# SAMV71_Xplained_Ultra_Audio.net
KiCad netlist of a schematic drawn in Altium Designer
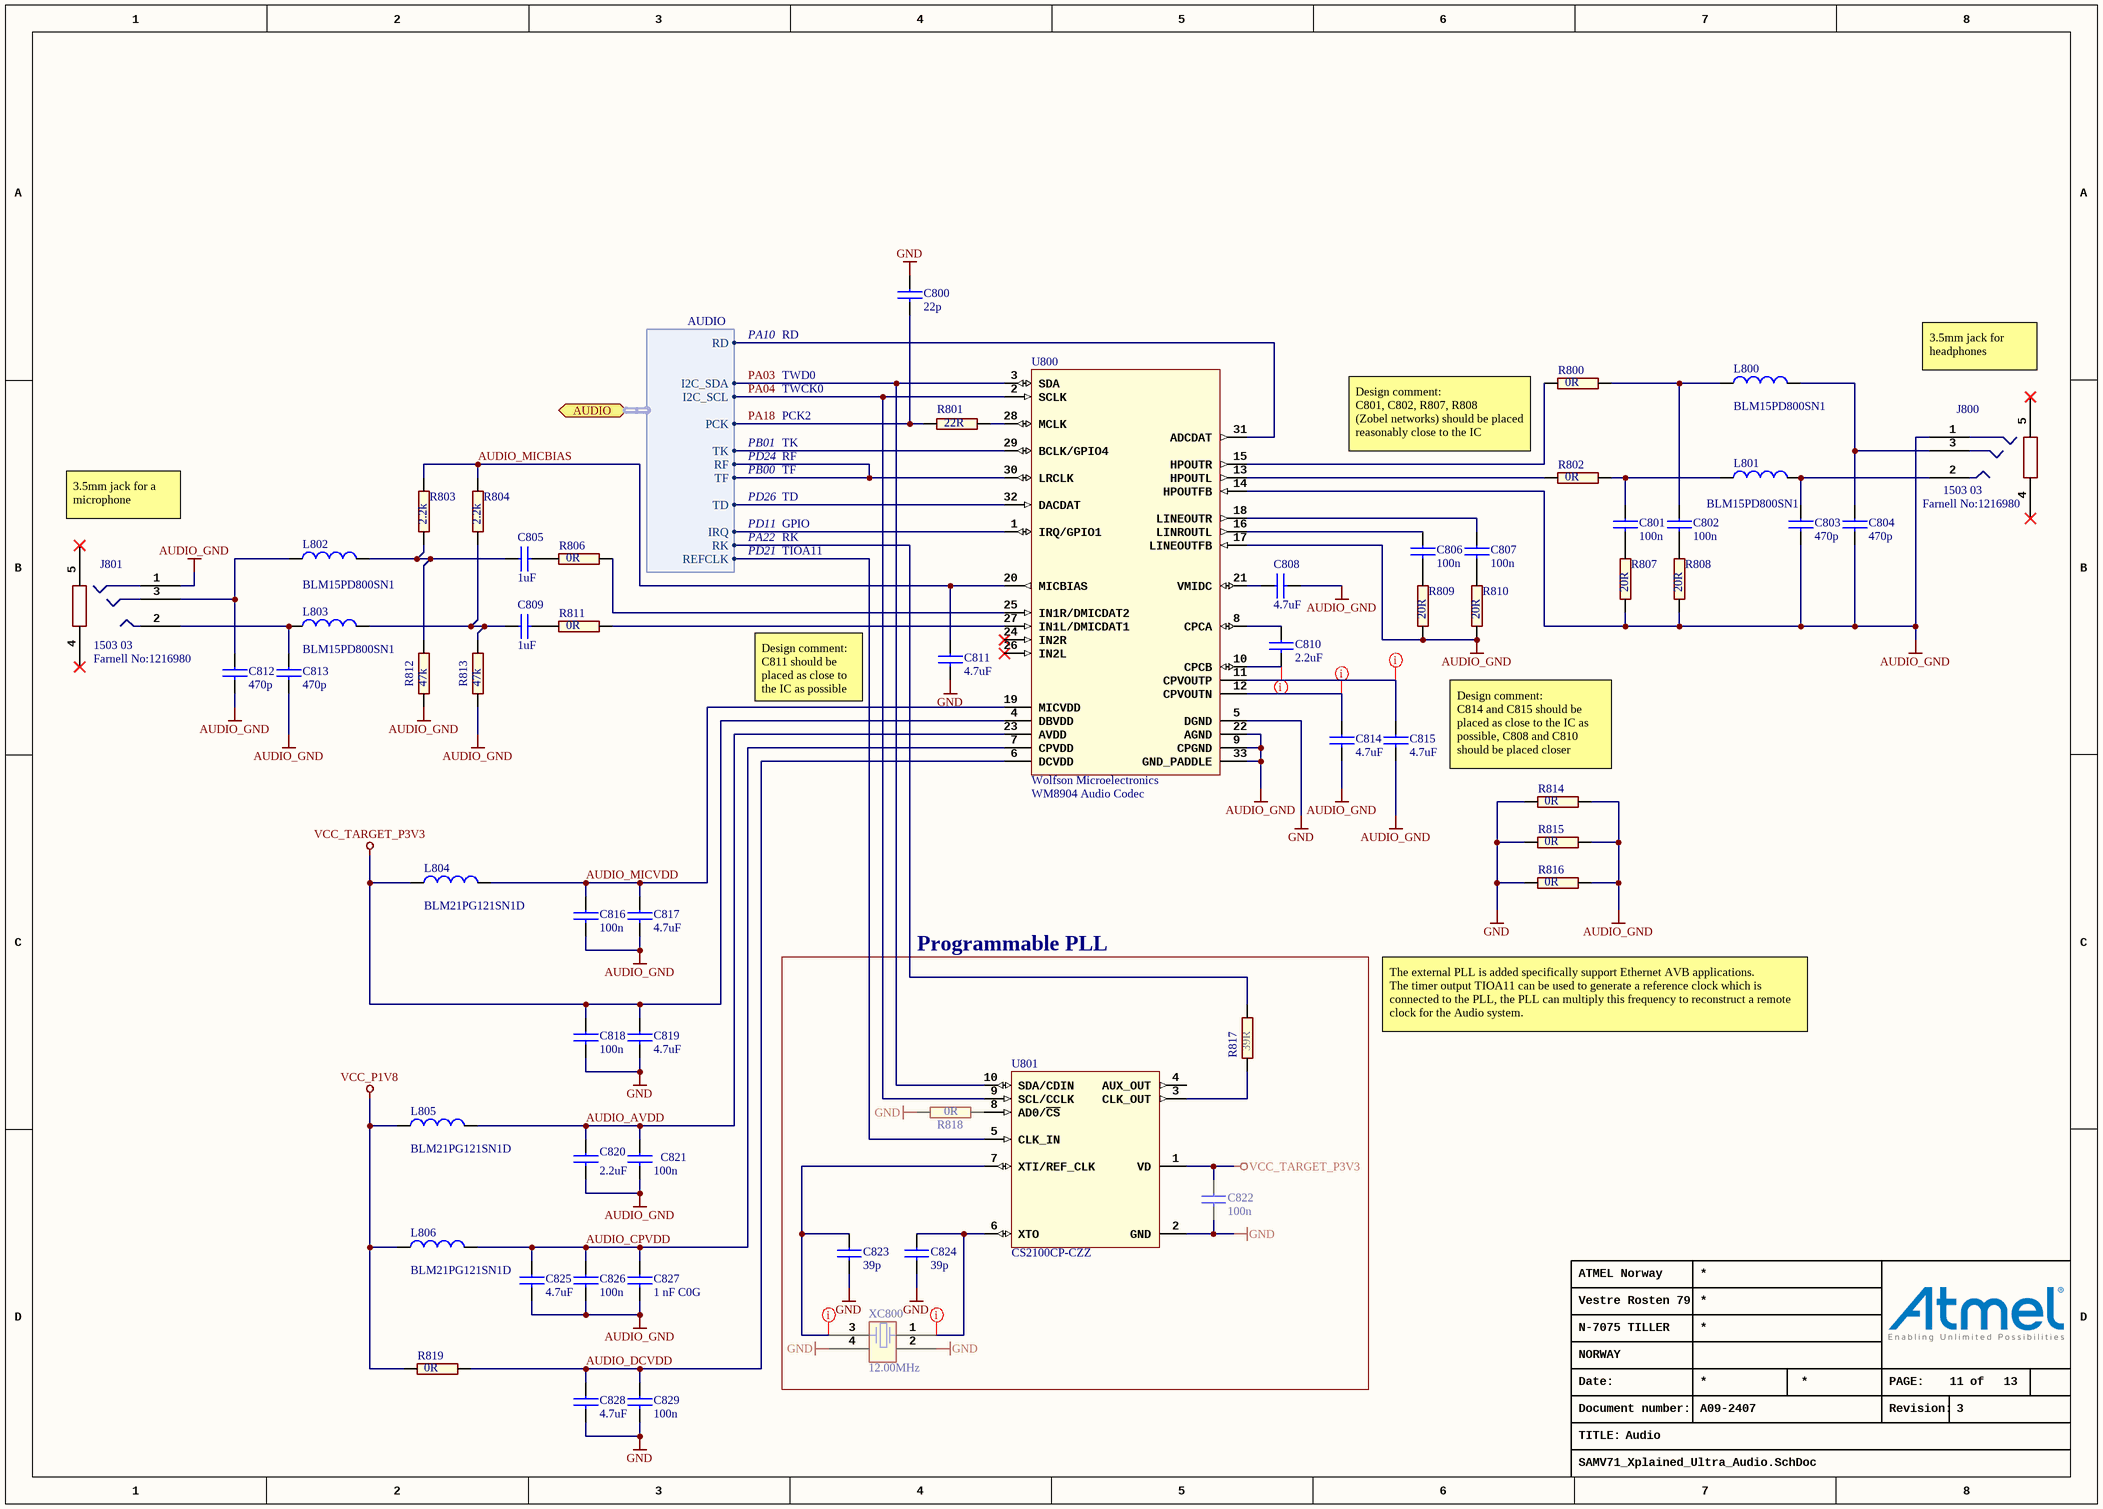
[diagram p0: SAMV71_Xplained_Ultra_Audio.SchDoc]

(export (version "E")
  (design (tool "Eeschema 10.0.6"))
  (components
    (comp (ref "C800")
      (value "22p")
      (footprint "AP1-00001")
      (description "Ceramic capacitor, SMD 0402, NP0, 50V, +/-5%")
      (fields (field (name "TOLERANCE") "50V, +/-5%"))
      (libsource (lib "AltiumDbLib") (part "CAP-NONPOL"))
    )
    (comp (ref "C801")
      (value "100n")
      (footprint "AP1-00001")
      (description "Ceramic capacitor, SMD 0402, X7R, 16V, +/-10%")
      (fields (field (name "TOLERANCE") "16V, +/-10%") (field (name "MANUFACTURER") "Kemet"))
      (libsource (lib "AltiumDbLib") (part "CAP-NONPOL"))
    )
    (comp (ref "C802")
      (value "100n")
      (footprint "AP1-00001")
      (description "Ceramic capacitor, SMD 0402, X7R, 16V, +/-10%")
      (fields (field (name "TOLERANCE") "16V, +/-10%") (field (name "MANUFACTURER") "Kemet"))
      (libsource (lib "AltiumDbLib") (part "CAP-NONPOL"))
    )
    (comp (ref "C803")
      (value "470p")
      (footprint "AP1-00001")
      (description "Ceramic capacitor, SMD 0402, X7R, 50V, +/-10%")
      (fields (field (name "TOLERANCE") "50V, +/-10%"))
      (libsource (lib "AltiumDbLib") (part "CAP-NONPOL"))
    )
    (comp (ref "C804")
      (value "470p")
      (footprint "AP1-00001")
      (description "Ceramic capacitor, SMD 0402, X7R, 50V, +/-10%")
      (fields (field (name "TOLERANCE") "50V, +/-10%"))
      (libsource (lib "AltiumDbLib") (part "CAP-NONPOL"))
    )
    (comp (ref "C805")
      (value "1uF")
      (footprint "AP1-00038")
      (description "Ceramic capacitor, SMD 0402, X5R, 10V, ±10 %")
      (fields (field (name "MANUFACTURER") "AVX") (field (name "MPN") "0402ZD105KAT2A"))
      (libsource (lib "AltiumDbLib") (part "CAP-NONPOL"))
    )
    (comp (ref "C806")
      (value "100n")
      (footprint "AP1-00001")
      (description "Ceramic capacitor, SMD 0402, X7R, 16V, +/-10%")
      (fields (field (name "TOLERANCE") "16V, +/-10%") (field (name "MANUFACTURER") "Kemet"))
      (libsource (lib "AltiumDbLib") (part "CAP-NONPOL"))
    )
    (comp (ref "C807")
      (value "100n")
      (footprint "AP1-00001")
      (description "Ceramic capacitor, SMD 0402, X7R, 16V, +/-10%")
      (fields (field (name "TOLERANCE") "16V, +/-10%") (field (name "MANUFACTURER") "Kemet"))
      (libsource (lib "AltiumDbLib") (part "CAP-NONPOL"))
    )
    (comp (ref "C808")
      (value "4.7uF")
      (footprint "AP1-00039")
      (description "Ceramic capacitor, SMD 0603, X5R, 10V, 10% (de31036)")
      (fields (field (name "TOLERANCE") "10%") (field (name "MANUFACTURER") "tdk"))
      (libsource (lib "AltiumDbLib") (part "CAP-NONPOL"))
    )
    (comp (ref "C809")
      (value "1uF")
      (footprint "AP1-00038")
      (description "Ceramic capacitor, SMD 0402, X5R, 10V, ±10 %")
      (fields (field (name "MANUFACTURER") "AVX") (field (name "MPN") "0402ZD105KAT2A"))
      (libsource (lib "AltiumDbLib") (part "CAP-NONPOL"))
    )
    (comp (ref "C810")
      (value "2.2uF")
      (footprint "AP1-00001")
      (description "Ceramic capacitor, SMD 0402, X5R, 6.3V, +/-20%")
      (fields (field (name "TOLERANCE") "Â±20%") (field (name "MANUFACTURER") "Kemet"))
      (libsource (lib "AltiumDbLib") (part "CAP-NONPOL"))
    )
    (comp (ref "C811")
      (value "4.7uF")
      (footprint "AP1-00039")
      (description "Ceramic capacitor, SMD 0603, X5R, 10V, 10% (de31036)")
      (fields (field (name "TOLERANCE") "10%") (field (name "MANUFACTURER") "tdk"))
      (libsource (lib "AltiumDbLib") (part "CAP-NONPOL"))
    )
    (comp (ref "C812")
      (value "470p")
      (footprint "AP1-00001")
      (description "Ceramic capacitor, SMD 0402, X7R, 50V, +/-10%")
      (fields (field (name "TOLERANCE") "50V, +/-10%"))
      (libsource (lib "AltiumDbLib") (part "CAP-NONPOL"))
    )
    (comp (ref "C813")
      (value "470p")
      (footprint "AP1-00001")
      (description "Ceramic capacitor, SMD 0402, X7R, 50V, +/-10%")
      (fields (field (name "TOLERANCE") "50V, +/-10%"))
      (libsource (lib "AltiumDbLib") (part "CAP-NONPOL"))
    )
    (comp (ref "C814")
      (value "4.7uF")
      (footprint "AP1-00001")
      (description "Ceramic capacitor, SMD 0402, X5R, 6.3V, +/-20% (de33687)")
      (fields (field (name "TOLERANCE") "+-20%") (field (name "MANUFACTURER") "Murata"))
      (libsource (lib "AltiumDbLib") (part "CAP-NONPOL"))
    )
    (comp (ref "C815")
      (value "4.7uF")
      (footprint "AP1-00001")
      (description "Ceramic capacitor, SMD 0402, X5R, 6.3V, +/-20% (de33687)")
      (fields (field (name "TOLERANCE") "+-20%") (field (name "MANUFACTURER") "Murata"))
      (libsource (lib "AltiumDbLib") (part "CAP-NONPOL"))
    )
    (comp (ref "C816")
      (value "100n")
      (footprint "AP1-00001")
      (description "Ceramic capacitor, SMD 0402, X7R, 16V, +/-10%")
      (fields (field (name "TOLERANCE") "16V, +/-10%") (field (name "MANUFACTURER") "Kemet"))
      (libsource (lib "AltiumDbLib") (part "CAP-NONPOL"))
    )
    (comp (ref "C817")
      (value "4.7uF")
      (footprint "AP1-00039")
      (description "Ceramic capacitor, SMD 0603, X5R, 10V, 10% (de31036)")
      (fields (field (name "TOLERANCE") "10%") (field (name "MANUFACTURER") "tdk"))
      (libsource (lib "AltiumDbLib") (part "CAP-NONPOL"))
    )
    (comp (ref "C818")
      (value "100n")
      (footprint "AP1-00001")
      (description "Ceramic capacitor, SMD 0402, X7R, 16V, +/-10%")
      (fields (field (name "TOLERANCE") "16V, +/-10%") (field (name "MANUFACTURER") "Kemet"))
      (libsource (lib "AltiumDbLib") (part "CAP-NONPOL"))
    )
    (comp (ref "C819")
      (value "4.7uF")
      (footprint "AP1-00039")
      (description "Ceramic capacitor, SMD 0603, X5R, 10V, 10% (de31036)")
      (fields (field (name "TOLERANCE") "10%") (field (name "MANUFACTURER") "tdk"))
      (libsource (lib "AltiumDbLib") (part "CAP-NONPOL"))
    )
    (comp (ref "C820")
      (value "2.2uF")
      (footprint "AP1-00001")
      (description "Ceramic capacitor, SMD 0402, X5R, 6.3V, +/-20%")
      (fields (field (name "TOLERANCE") "Â±20%") (field (name "MANUFACTURER") "Kemet"))
      (libsource (lib "AltiumDbLib") (part "CAP-NONPOL"))
    )
    (comp (ref "C821")
      (value "100n")
      (footprint "AP1-00001")
      (description "Ceramic capacitor, SMD 0402, X7R, 16V, +/-10%")
      (fields (field (name "TOLERANCE") "16V, +/-10%") (field (name "MANUFACTURER") "Kemet"))
      (libsource (lib "AltiumDbLib") (part "CAP-NONPOL"))
    )
    (comp (ref "C822")
      (value "100n")
      (footprint "AP1-00001")
      (description "Ceramic capacitor, SMD 0402, X7R, 16V, +/-10%")
      (fields (field (name "TOLERANCE") "16V, +/-10%") (field (name "MANUFACTURER") "Kemet"))
      (libsource (lib "AltiumDbLib") (part "CAP-NONPOL"))
    )
    (comp (ref "C823")
      (value "39p")
      (footprint "AP1-00001")
      (description "Ceramic capacitor, SMD 0402, NP0, 50V, +/-5%")
      (fields (field (name "TOLERANCE") "50V, +/-5%"))
      (libsource (lib "AltiumDbLib") (part "CAP-NONPOL"))
    )
    (comp (ref "C824")
      (value "39p")
      (footprint "AP1-00001")
      (description "Ceramic capacitor, SMD 0402, NP0, 50V, +/-5%")
      (fields (field (name "TOLERANCE") "50V, +/-5%"))
      (libsource (lib "AltiumDbLib") (part "CAP-NONPOL"))
    )
    (comp (ref "C825")
      (value "4.7uF")
      (footprint "AP1-00039")
      (description "Ceramic capacitor, SMD 0603, X5R, 10V, 10% (de31036)")
      (fields (field (name "TOLERANCE") "10%") (field (name "MANUFACTURER") "tdk"))
      (libsource (lib "AltiumDbLib") (part "CAP-NONPOL"))
    )
    (comp (ref "C826")
      (value "100n")
      (footprint "AP1-00001")
      (description "Ceramic capacitor, SMD 0402, X7R, 16V, +/-10%")
      (fields (field (name "TOLERANCE") "16V, +/-10%") (field (name "MANUFACTURER") "Kemet"))
      (libsource (lib "AltiumDbLib") (part "CAP-NONPOL"))
    )
    (comp (ref "C827")
      (value "1 nF C0G")
      (footprint "AP1-00001")
      (description "Ceramic capacitor, SMD 0402, C0G, 50V, +/-5%")
      (fields (field (name "TOLERANCE") "5%") (field (name "MANUFACTURER") "Murata"))
      (libsource (lib "AltiumDbLib") (part "CAP-NONPOL"))
    )
    (comp (ref "C828")
      (value "4.7uF")
      (footprint "AP1-00039")
      (description "Ceramic capacitor, SMD 0603, X5R, 10V, 10% (de31036)")
      (fields (field (name "TOLERANCE") "10%") (field (name "MANUFACTURER") "tdk"))
      (libsource (lib "AltiumDbLib") (part "CAP-NONPOL"))
    )
    (comp (ref "C829")
      (value "100n")
      (footprint "AP1-00001")
      (description "Ceramic capacitor, SMD 0402, X7R, 16V, +/-10%")
      (fields (field (name "TOLERANCE") "16V, +/-10%") (field (name "MANUFACTURER") "Kemet"))
      (libsource (lib "AltiumDbLib") (part "CAP-NONPOL"))
    )
    (comp (ref "J800")
      (value "Farnell No:1216980")
      (footprint "AP8-00397")
      (description "3.5mm stereo phone jack")
      (fields
        (field (name "ALTIUM_VALUE") "1503 03")
        (field (name "MANUFACTURER") "Lumberg")
        (field (name "MPN") "1503 03")
      )
      (libsource (lib "") (part "Jack_Stereo_1503_03_1"))
    )
    (comp (ref "J801")
      (value "Farnell No:1216980")
      (footprint "AP8-00397")
      (description "3.5mm stereo phone jack")
      (fields
        (field (name "ALTIUM_VALUE") "1503 03")
        (field (name "MANUFACTURER") "Lumberg")
        (field (name "MPN") "1503 03")
      )
      (libsource (lib "AltiumDbLib") (part "Jack_Stereo_1503_03"))
    )
    (comp (ref "L800")
      (value "BLM15PD800SN1")
      (footprint "AP3-00028")
      (description "FERRITE CHIP 80 OHM 1500MA 0402")
      (fields (field (name "TOLERANCE") "±25%") (field (name "MANUFACTURER") "Murata"))
      (libsource (lib "AltiumDbLib") (part "INDUCTOR"))
    )
    (comp (ref "L801")
      (value "BLM15PD800SN1")
      (footprint "AP3-00028")
      (description "FERRITE CHIP 80 OHM 1500MA 0402")
      (fields (field (name "TOLERANCE") "±25%") (field (name "MANUFACTURER") "Murata"))
      (libsource (lib "AltiumDbLib") (part "INDUCTOR"))
    )
    (comp (ref "L802")
      (value "BLM15PD800SN1")
      (footprint "AP3-00028")
      (description "FERRITE CHIP 80 OHM 1500MA 0402")
      (fields (field (name "TOLERANCE") "±25%") (field (name "MANUFACTURER") "Murata"))
      (libsource (lib "AltiumDbLib") (part "INDUCTOR"))
    )
    (comp (ref "L803")
      (value "BLM15PD800SN1")
      (footprint "AP3-00028")
      (description "FERRITE CHIP 80 OHM 1500MA 0402")
      (fields (field (name "TOLERANCE") "±25%") (field (name "MANUFACTURER") "Murata"))
      (libsource (lib "AltiumDbLib") (part "INDUCTOR"))
    )
    (comp (ref "L804")
      (value "BLM21PG121SN1D")
      (footprint "AP3-00104")
      (fields (field (name "MANUFACTURER") "Murata"))
      (libsource (lib "AltiumDbLib") (part "INDUCTOR"))
    )
    (comp (ref "L805")
      (value "BLM21PG121SN1D")
      (footprint "AP3-00104")
      (fields (field (name "MANUFACTURER") "Murata"))
      (libsource (lib "AltiumDbLib") (part "INDUCTOR"))
    )
    (comp (ref "L806")
      (value "BLM21PG121SN1D")
      (footprint "AP3-00104")
      (fields (field (name "MANUFACTURER") "Murata"))
      (libsource (lib "AltiumDbLib") (part "INDUCTOR"))
    )
    (comp (ref "R800")
      (value "0R")
      (footprint "AP2-00000")
      (description "RES 0.0 OHM 1/16W 0402 SMD")
      (fields (field (name "TOLERANCE") "1 %") (field (name "MANUFACTURER") "(n/a)"))
      (libsource (lib "AltiumDbLib") (part "R2"))
    )
    (comp (ref "R801")
      (value "22R")
      (footprint "AP2-00000")
      (description "Thick film resistor, SMD 0402, 1/16W, 1% (de23607)")
      (fields (field (name "TOLERANCE") "1 %") (field (name "MANUFACTURER") "Samsung"))
      (libsource (lib "AltiumDbLib") (part "R2"))
    )
    (comp (ref "R802")
      (value "0R")
      (footprint "AP2-00000")
      (description "RES 0.0 OHM 1/16W 0402 SMD")
      (fields (field (name "TOLERANCE") "1 %") (field (name "MANUFACTURER") "(n/a)"))
      (libsource (lib "AltiumDbLib") (part "R2"))
    )
    (comp (ref "R803")
      (value "2.2k")
      (footprint "AP2-00000")
      (description "Thick film resistor, SMD 0402, 1/16W, 1%")
      (fields (field (name "TOLERANCE") "1 %"))
      (libsource (lib "") (part "R2_1"))
    )
    (comp (ref "R804")
      (value "2.2k")
      (footprint "AP2-00000")
      (description "Thick film resistor, SMD 0402, 1/16W, 1%")
      (fields (field (name "TOLERANCE") "1 %"))
      (libsource (lib "") (part "R2_1"))
    )
    (comp (ref "R806")
      (value "0R")
      (footprint "AP2-00000")
      (description "RES 0.0 OHM 1/16W 0402 SMD")
      (fields (field (name "TOLERANCE") "1 %") (field (name "MANUFACTURER") "(n/a)"))
      (libsource (lib "AltiumDbLib") (part "R2"))
    )
    (comp (ref "R807")
      (value "20R")
      (footprint "AP2-00000")
      (description "Thick film resistor, SMD 0402, 1/16W, 1%")
      (fields (field (name "TOLERANCE") "1 %"))
      (libsource (lib "") (part "R2_1"))
    )
    (comp (ref "R808")
      (value "20R")
      (footprint "AP2-00000")
      (description "Thick film resistor, SMD 0402, 1/16W, 1%")
      (fields (field (name "TOLERANCE") "1 %"))
      (libsource (lib "") (part "R2_1"))
    )
    (comp (ref "R809")
      (value "20R")
      (footprint "AP2-00000")
      (description "Thick film resistor, SMD 0402, 1/16W, 1%")
      (fields (field (name "TOLERANCE") "1 %"))
      (libsource (lib "") (part "R2_1"))
    )
    (comp (ref "R810")
      (value "20R")
      (footprint "AP2-00000")
      (description "Thick film resistor, SMD 0402, 1/16W, 1%")
      (fields (field (name "TOLERANCE") "1 %"))
      (libsource (lib "") (part "R2_1"))
    )
    (comp (ref "R811")
      (value "0R")
      (footprint "AP2-00000")
      (description "RES 0.0 OHM 1/16W 0402 SMD")
      (fields (field (name "TOLERANCE") "1 %") (field (name "MANUFACTURER") "(n/a)"))
      (libsource (lib "AltiumDbLib") (part "R2"))
    )
    (comp (ref "R812")
      (value "47k")
      (footprint "AP2-00000")
      (description "Thick film resistor, SMD 0402, 1/16W, 1%")
      (fields (field (name "TOLERANCE") "1 %"))
      (libsource (lib "") (part "R2_1"))
    )
    (comp (ref "R813")
      (value "47k")
      (footprint "AP2-00000")
      (description "Thick film resistor, SMD 0402, 1/16W, 1%")
      (fields (field (name "TOLERANCE") "1 %"))
      (libsource (lib "") (part "R2_1"))
    )
    (comp (ref "R814")
      (value "0R")
      (footprint "AP2-00000")
      (description "RES 0.0 OHM 1/16W 0402 SMD")
      (fields (field (name "TOLERANCE") "1 %") (field (name "MANUFACTURER") "(n/a)"))
      (libsource (lib "AltiumDbLib") (part "R2"))
    )
    (comp (ref "R815")
      (value "0R")
      (footprint "AP2-00000")
      (description "RES 0.0 OHM 1/16W 0402 SMD")
      (fields (field (name "TOLERANCE") "1 %") (field (name "MANUFACTURER") "(n/a)"))
      (libsource (lib "AltiumDbLib") (part "R2"))
    )
    (comp (ref "R816")
      (value "0R")
      (footprint "AP2-00000")
      (description "RES 0.0 OHM 1/16W 0402 SMD")
      (fields (field (name "TOLERANCE") "1 %") (field (name "MANUFACTURER") "(n/a)"))
      (libsource (lib "AltiumDbLib") (part "R2"))
    )
    (comp (ref "R817")
      (value "39R")
      (footprint "AP2-00000")
      (description "Thick film resistor, SMD 0402, 1/16W, 1%")
      (fields (field (name "TOLERANCE") "1 %"))
      (libsource (lib "") (part "R2_1"))
    )
    (comp (ref "R818")
      (value "0R")
      (footprint "AP2-00000")
      (description "RES 0.0 OHM 1/16W 0402 SMD")
      (fields (field (name "TOLERANCE") "1 %") (field (name "MANUFACTURER") "(n/a)"))
      (libsource (lib "AltiumDbLib") (part "R2"))
    )
    (comp (ref "R819")
      (value "0R")
      (footprint "AP2-00000")
      (description "RES 0.0 OHM 1/16W 0402 SMD")
      (fields (field (name "TOLERANCE") "1 %") (field (name "MANUFACTURER") "(n/a)"))
      (libsource (lib "AltiumDbLib") (part "R2"))
    )
    (comp (ref "U800")
      (value "Wolfson Microelectronics")
      (footprint "AP6-00420")
      (description "Ultra Low Power Codec for Portable Audio Applications")
      (fields
        (field (name "ALTIUM_VALUE") "WM8904 Audio Codec")
        (field (name "MANUFACTURER") "Wolfson microelectronics")
        (field (name "MPN") "WM8904CGEFL/RV")
      )
      (libsource (lib "AltiumDbLib") (part "WM8904"))
    )
    (comp (ref "U801")
      (value "CS2100CP-CZZ")
      (footprint "AP6-00097")
      (description "Programmable Phase-Locked Loop Clock Generator")
      (fields (field (name "MANUFACTURER") "CIRRUS LOGIC") (field (name "MPN") "CS2100CP-CZZR"))
      (libsource (lib "AltiumDbLib") (part "CS2100"))
    )
    (comp (ref "XC800")
      (value "12.00MHz")
      (footprint "AP7-00039")
      (description "Fox FQ5032B 12.0MHz SMD crystal 738B-12")
      (fields (field (name "TOLERANCE") "Â±30ppm") (field (name "MANUFACTURER") "Fox  Electronics"))
      (libsource (lib "AltiumDbLib") (part "CRYSTAL1324"))
    )
  )
  (nets
    (net (code "2") (name "/AUDIO_AVDD") (class "Default")
      (node (ref "C820") (pin "1") (pinfunction "1_1") (pintype "passive"))
      (node (ref "C821") (pin "1") (pinfunction "1_1") (pintype "passive"))
      (node (ref "L805") (pin "2") (pinfunction "2_2") (pintype "passive"))
      (node (ref "U800") (pin "23") (pinfunction "AVDD_23") (pintype "power_in"))
    )
    (net (code "3") (name "/AUDIO_CPVDD") (class "Default")
      (node (ref "C825") (pin "1") (pinfunction "1_1") (pintype "passive"))
      (node (ref "C826") (pin "1") (pinfunction "1_1") (pintype "passive"))
      (node (ref "C827") (pin "1") (pinfunction "1_1") (pintype "passive"))
      (node (ref "L806") (pin "2") (pinfunction "2_2") (pintype "passive"))
      (node (ref "U800") (pin "7") (pinfunction "CPVDD_7") (pintype "power_in"))
    )
    (net (code "4") (name "/AUDIO_DCVDD") (class "Default")
      (node (ref "C828") (pin "1") (pinfunction "1_1") (pintype "passive"))
      (node (ref "C829") (pin "1") (pinfunction "1_1") (pintype "passive"))
      (node (ref "R819") (pin "2") (pinfunction "2_2") (pintype "passive"))
      (node (ref "U800") (pin "6") (pinfunction "DCVDD_6") (pintype "power_in"))
    )
    (net (code "5") (name "/AUDIO_MICBIAS") (class "Default")
      (node (ref "C811") (pin "1") (pinfunction "1_1") (pintype "passive"))
      (node (ref "R803") (pin "2") (pinfunction "2_2") (pintype "passive"))
      (node (ref "R804") (pin "2") (pinfunction "2_2") (pintype "passive"))
      (node (ref "U800") (pin "20") (pinfunction "MICBIAS_20") (pintype "output"))
    )
    (net (code "6") (name "/AUDIO_MICVDD") (class "Default")
      (node (ref "C816") (pin "1") (pinfunction "1_1") (pintype "passive"))
      (node (ref "C817") (pin "1") (pinfunction "1_1") (pintype "passive"))
      (node (ref "L804") (pin "2") (pinfunction "2_2") (pintype "passive"))
      (node (ref "U800") (pin "19") (pinfunction "MICVDD_19") (pintype "power_in"))
    )
    (net (code "7") (name "/IRQ") (class "Default")
      (node (ref "U800") (pin "1") (pinfunction "IRQ/GPIO1_1") (pintype "bidirectional"))
    )
    (net (code "8") (name "/PA03") (class "Default")
      (node (ref "U800") (pin "3") (pinfunction "SDA_3") (pintype "bidirectional"))
      (node (ref "U801") (pin "10") (pinfunction "SDA/CDIN_10") (pintype "bidirectional"))
    )
    (net (code "9") (name "/PA04") (class "Default")
      (node (ref "U800") (pin "2") (pinfunction "SCLK_2") (pintype "input"))
      (node (ref "U801") (pin "9") (pinfunction "SCL/CCLK_9") (pintype "input"))
    )
    (net (code "10") (name "/PA18") (class "Default")
      (node (ref "C800") (pin "2") (pinfunction "2_2") (pintype "passive"))
      (node (ref "R801") (pin "1") (pinfunction "1_1") (pintype "passive"))
    )
    (net (code "11") (name "/RD") (class "Default")
      (node (ref "U800") (pin "31") (pinfunction "ADCDAT_31") (pintype "output"))
    )
    (net (code "12") (name "/REFCLK") (class "Default")
      (node (ref "U801") (pin "5") (pinfunction "CLK_IN_5") (pintype "input"))
    )
    (net (code "13") (name "/RF") (class "Default")
      (node (ref "U800") (pin "30") (pinfunction "LRCLK_30") (pintype "bidirectional"))
    )
    (net (code "14") (name "/RK") (class "Default")
      (node (ref "R817") (pin "2") (pinfunction "2_2") (pintype "passive"))
    )
    (net (code "15") (name "/TD") (class "Default")
      (node (ref "U800") (pin "32") (pinfunction "DACDAT_32") (pintype "input"))
    )
    (net (code "16") (name "/TK") (class "Default")
      (node (ref "U800") (pin "29") (pinfunction "BCLK/GPIO4_29") (pintype "bidirectional"))
    )
    (net (code "18") (name "AUDIO_GND") (class "Default")
      (node (ref "C803") (pin "2") (pinfunction "2_2") (pintype "passive"))
      (node (ref "C804") (pin "2") (pinfunction "2_2") (pintype "passive"))
      (node (ref "C808") (pin "2") (pinfunction "2_2") (pintype "passive"))
      (node (ref "C812") (pin "2") (pinfunction "2_2") (pintype "passive"))
      (node (ref "C813") (pin "2") (pinfunction "2_2") (pintype "passive"))
      (node (ref "C814") (pin "2") (pinfunction "2_2") (pintype "passive"))
      (node (ref "C815") (pin "2") (pinfunction "2_2") (pintype "passive"))
      (node (ref "C816") (pin "2") (pinfunction "2_2") (pintype "passive"))
      (node (ref "C817") (pin "2") (pinfunction "2_2") (pintype "passive"))
      (node (ref "C820") (pin "2") (pinfunction "2_2") (pintype "passive"))
      (node (ref "C821") (pin "2") (pinfunction "2_2") (pintype "passive"))
      (node (ref "C825") (pin "2") (pinfunction "2_2") (pintype "passive"))
      (node (ref "C826") (pin "2") (pinfunction "2_2") (pintype "passive"))
      (node (ref "C827") (pin "2") (pinfunction "2_2") (pintype "passive"))
      (node (ref "J800") (pin "1") (pinfunction "GND_1") (pintype "passive"))
      (node (ref "J801") (pin "1") (pinfunction "GND_1") (pintype "passive"))
      (node (ref "R807") (pin "1") (pinfunction "1_1") (pintype "passive"))
      (node (ref "R808") (pin "1") (pinfunction "1_1") (pintype "passive"))
      (node (ref "R809") (pin "1") (pinfunction "1_1") (pintype "passive"))
      (node (ref "R810") (pin "1") (pinfunction "1_1") (pintype "passive"))
      (node (ref "R812") (pin "1") (pinfunction "1_1") (pintype "passive"))
      (node (ref "R813") (pin "1") (pinfunction "1_1") (pintype "passive"))
      (node (ref "R814") (pin "2") (pinfunction "2_2") (pintype "passive"))
      (node (ref "R815") (pin "2") (pinfunction "2_2") (pintype "passive"))
      (node (ref "R816") (pin "2") (pinfunction "2_2") (pintype "passive"))
      (node (ref "U800") (pin "14") (pinfunction "HPOUTFB_14") (pintype "input"))
      (node (ref "U800") (pin "17") (pinfunction "LINEOUTFB_17") (pintype "input"))
      (node (ref "U800") (pin "22") (pinfunction "AGND_22") (pintype "power_in"))
      (node (ref "U800") (pin "33") (pinfunction "GND_PADDLE_33") (pintype "power_in"))
      (node (ref "U800") (pin "9") (pinfunction "CPGND_9") (pintype "power_in"))
    )
    (net (code "19") (name "GND") (class "Default")
      (node (ref "C800") (pin "1") (pinfunction "1_1") (pintype "passive"))
      (node (ref "C811") (pin "2") (pinfunction "2_2") (pintype "passive"))
      (node (ref "C818") (pin "2") (pinfunction "2_2") (pintype "passive"))
      (node (ref "C819") (pin "2") (pinfunction "2_2") (pintype "passive"))
      (node (ref "C822") (pin "2") (pinfunction "2_2") (pintype "passive"))
      (node (ref "C823") (pin "2") (pinfunction "2_2") (pintype "passive"))
      (node (ref "C824") (pin "2") (pinfunction "2_2") (pintype "passive"))
      (node (ref "C828") (pin "2") (pinfunction "2_2") (pintype "passive"))
      (node (ref "C829") (pin "2") (pinfunction "2_2") (pintype "passive"))
      (node (ref "R814") (pin "1") (pinfunction "1_1") (pintype "passive"))
      (node (ref "R815") (pin "1") (pinfunction "1_1") (pintype "passive"))
      (node (ref "R816") (pin "1") (pinfunction "1_1") (pintype "passive"))
      (node (ref "R818") (pin "1") (pinfunction "1_1") (pintype "passive"))
      (node (ref "U800") (pin "5") (pinfunction "DGND_5") (pintype "power_in"))
      (node (ref "U801") (pin "2") (pinfunction "GND_2") (pintype "power_in"))
      (node (ref "XC800") (pin "2") (pinfunction "2_2") (pintype "passive"))
      (node (ref "XC800") (pin "4") (pinfunction "4_4") (pintype "passive"))
    )
    (net (code "20") (name "Net-(C801-Pad1)") (class "Default")
      (node (ref "C801") (pin "1") (pinfunction "1_1") (pintype "passive"))
      (node (ref "L801") (pin "1") (pinfunction "1_1") (pintype "passive"))
      (node (ref "R802") (pin "2") (pinfunction "2_2") (pintype "passive"))
    )
    (net (code "21") (name "Net-(C801-Pad2)") (class "Default")
      (node (ref "C801") (pin "2") (pinfunction "2_2") (pintype "passive"))
      (node (ref "R807") (pin "2") (pinfunction "2_2") (pintype "passive"))
    )
    (net (code "22") (name "Net-(C802-Pad1)") (class "Default")
      (node (ref "C802") (pin "1") (pinfunction "1_1") (pintype "passive"))
      (node (ref "L800") (pin "1") (pinfunction "1_1") (pintype "passive"))
      (node (ref "R800") (pin "2") (pinfunction "2_2") (pintype "passive"))
    )
    (net (code "23") (name "Net-(C802-Pad2)") (class "Default")
      (node (ref "C802") (pin "2") (pinfunction "2_2") (pintype "passive"))
      (node (ref "R808") (pin "2") (pinfunction "2_2") (pintype "passive"))
    )
    (net (code "24") (name "Net-(C803-Pad1)") (class "Default")
      (node (ref "C803") (pin "1") (pinfunction "1_1") (pintype "passive"))
      (node (ref "J800") (pin "2") (pintype "passive"))
      (node (ref "L801") (pin "2") (pinfunction "2_2") (pintype "passive"))
    )
    (net (code "25") (name "Net-(C804-Pad1)") (class "Default")
      (node (ref "C804") (pin "1") (pinfunction "1_1") (pintype "passive"))
      (node (ref "J800") (pin "3") (pintype "passive"))
      (node (ref "L800") (pin "2") (pinfunction "2_2") (pintype "passive"))
    )
    (net (code "26") (name "Net-(C805-Pad1)") (class "Default")
      (node (ref "C805") (pin "1") (pinfunction "1_1") (pintype "passive"))
      (node (ref "L802") (pin "2") (pinfunction "2_2") (pintype "passive"))
      (node (ref "R803") (pin "1") (pinfunction "1_1") (pintype "passive"))
      (node (ref "R812") (pin "2") (pinfunction "2_2") (pintype "passive"))
    )
    (net (code "27") (name "Net-(C805-Pad2)") (class "Default")
      (node (ref "C805") (pin "2") (pinfunction "2_2") (pintype "passive"))
      (node (ref "R806") (pin "1") (pinfunction "1_1") (pintype "passive"))
    )
    (net (code "28") (name "Net-(C806-Pad2)") (class "Default")
      (node (ref "C806") (pin "2") (pinfunction "2_2") (pintype "passive"))
      (node (ref "R809") (pin "2") (pinfunction "2_2") (pintype "passive"))
    )
    (net (code "29") (name "Net-(C807-Pad2)") (class "Default")
      (node (ref "C807") (pin "2") (pinfunction "2_2") (pintype "passive"))
      (node (ref "R810") (pin "2") (pinfunction "2_2") (pintype "passive"))
    )
    (net (code "30") (name "Net-(C809-Pad1)") (class "Default")
      (node (ref "C809") (pin "1") (pinfunction "1_1") (pintype "passive"))
      (node (ref "L803") (pin "2") (pinfunction "2_2") (pintype "passive"))
      (node (ref "R804") (pin "1") (pinfunction "1_1") (pintype "passive"))
      (node (ref "R813") (pin "2") (pinfunction "2_2") (pintype "passive"))
    )
    (net (code "31") (name "Net-(C809-Pad2)") (class "Default")
      (node (ref "C809") (pin "2") (pinfunction "2_2") (pintype "passive"))
      (node (ref "R811") (pin "1") (pinfunction "1_1") (pintype "passive"))
    )
    (net (code "32") (name "Net-(C812-Pad1)") (class "Default")
      (node (ref "C812") (pin "1") (pinfunction "1_1") (pintype "passive"))
      (node (ref "J801") (pin "3") (pintype "passive"))
      (node (ref "L802") (pin "1") (pinfunction "1_1") (pintype "passive"))
    )
    (net (code "33") (name "Net-(C813-Pad1)") (class "Default")
      (node (ref "C813") (pin "1") (pinfunction "1_1") (pintype "passive"))
      (node (ref "J801") (pin "2") (pintype "passive"))
      (node (ref "L803") (pin "1") (pinfunction "1_1") (pintype "passive"))
    )
    (net (code "34") (name "Net-(U800-CPCA)") (class "Default")
      (node (ref "C810") (pin "1") (pinfunction "1_1") (pintype "passive"))
      (node (ref "U800") (pin "8") (pinfunction "CPCA_8") (pintype "bidirectional"))
    )
    (net (code "35") (name "Net-(U800-CPCB)") (class "Default")
      (node (ref "C810") (pin "2") (pinfunction "2_2") (pintype "passive"))
      (node (ref "U800") (pin "10") (pinfunction "CPCB_10") (pintype "bidirectional"))
    )
    (net (code "36") (name "Net-(U800-CPVOUTN)") (class "Default")
      (node (ref "C814") (pin "1") (pinfunction "1_1") (pintype "passive"))
      (node (ref "U800") (pin "12") (pinfunction "CPVOUTN_12") (pintype "passive"))
    )
    (net (code "37") (name "Net-(U800-CPVOUTP)") (class "Default")
      (node (ref "C815") (pin "1") (pinfunction "1_1") (pintype "passive"))
      (node (ref "U800") (pin "11") (pinfunction "CPVOUTP_11") (pintype "passive"))
    )
    (net (code "38") (name "Net-(U800-HPOUTL)") (class "Default")
      (node (ref "R802") (pin "1") (pinfunction "1_1") (pintype "passive"))
      (node (ref "U800") (pin "13") (pinfunction "HPOUTL_13") (pintype "output"))
    )
    (net (code "39") (name "Net-(U800-HPOUTR)") (class "Default")
      (node (ref "R800") (pin "1") (pinfunction "1_1") (pintype "passive"))
      (node (ref "U800") (pin "15") (pinfunction "HPOUTR_15") (pintype "output"))
    )
    (net (code "40") (name "Net-(U800-IN1L{slash}DMICDAT1)") (class "Default")
      (node (ref "R811") (pin "2") (pinfunction "2_2") (pintype "passive"))
      (node (ref "U800") (pin "27") (pinfunction "IN1L/DMICDAT1_27") (pintype "input"))
    )
    (net (code "41") (name "Net-(U800-IN1R{slash}DMICDAT2)") (class "Default")
      (node (ref "R806") (pin "2") (pinfunction "2_2") (pintype "passive"))
      (node (ref "U800") (pin "25") (pinfunction "IN1R/DMICDAT2_25") (pintype "input"))
    )
    (net (code "42") (name "Net-(U800-LINEOUTR)") (class "Default")
      (node (ref "C807") (pin "1") (pinfunction "1_1") (pintype "passive"))
      (node (ref "U800") (pin "18") (pinfunction "LINEOUTR_18") (pintype "output"))
    )
    (net (code "43") (name "Net-(U800-LINROUTL)") (class "Default")
      (node (ref "C806") (pin "1") (pinfunction "1_1") (pintype "passive"))
      (node (ref "U800") (pin "16") (pinfunction "LINROUTL_16") (pintype "output"))
    )
    (net (code "44") (name "Net-(U800-MCLK)") (class "Default")
      (node (ref "R801") (pin "2") (pinfunction "2_2") (pintype "passive"))
      (node (ref "U800") (pin "28") (pinfunction "MCLK_28") (pintype "bidirectional"))
    )
    (net (code "45") (name "Net-(U800-VMIDC)") (class "Default")
      (node (ref "C808") (pin "1") (pinfunction "1_1") (pintype "passive"))
      (node (ref "U800") (pin "21") (pinfunction "VMIDC_21") (pintype "bidirectional"))
    )
    (net (code "46") (name "Net-(U801-AD0{slash}~{CS})") (class "Default")
      (node (ref "R818") (pin "2") (pinfunction "2_2") (pintype "passive"))
      (node (ref "U801") (pin "8") (pinfunction "AD0/~{CS}_8") (pintype "input"))
    )
    (net (code "47") (name "Net-(U801-CLK_OUT)") (class "Default")
      (node (ref "R817") (pin "1") (pinfunction "1_1") (pintype "passive"))
      (node (ref "U801") (pin "3") (pinfunction "CLK_OUT_3") (pintype "output"))
    )
    (net (code "48") (name "Net-(U801-XTI{slash}REF_CLK)") (class "Default")
      (node (ref "C823") (pin "1") (pinfunction "1_1") (pintype "passive"))
      (node (ref "U801") (pin "7") (pinfunction "XTI/REF_CLK_7") (pintype "bidirectional"))
      (node (ref "XC800") (pin "3") (pinfunction "3_3") (pintype "passive"))
    )
    (net (code "49") (name "Net-(U801-XTO)") (class "Default")
      (node (ref "C824") (pin "1") (pinfunction "1_1") (pintype "passive"))
      (node (ref "U801") (pin "6") (pinfunction "XTO_6") (pintype "bidirectional"))
      (node (ref "XC800") (pin "1") (pinfunction "1_1") (pintype "passive"))
    )
    (net (code "50") (name "VCC_P1V8") (class "Default")
      (node (ref "L805") (pin "1") (pinfunction "1_1") (pintype "passive"))
      (node (ref "L806") (pin "1") (pinfunction "1_1") (pintype "passive"))
      (node (ref "R819") (pin "1") (pinfunction "1_1") (pintype "passive"))
    )
    (net (code "51") (name "VCC_TARGET_P3V3") (class "Default")
      (node (ref "C818") (pin "1") (pinfunction "1_1") (pintype "passive"))
      (node (ref "C819") (pin "1") (pinfunction "1_1") (pintype "passive"))
      (node (ref "C822") (pin "1") (pinfunction "1_1") (pintype "passive"))
      (node (ref "L804") (pin "1") (pinfunction "1_1") (pintype "passive"))
      (node (ref "U800") (pin "4") (pinfunction "DBVDD_4") (pintype "power_in"))
      (node (ref "U801") (pin "1") (pinfunction "VD_1") (pintype "power_in"))
    )
    (net (code "52") (name "unconnected-(J800-Pad4)") (class "Default")
      (node (ref "J800") (pin "4") (pintype "passive+no_connect"))
    )
    (net (code "53") (name "unconnected-(J800-Pad5)") (class "Default")
      (node (ref "J800") (pin "5") (pintype "passive+no_connect"))
    )
    (net (code "54") (name "unconnected-(J801-Pad4)") (class "Default")
      (node (ref "J801") (pin "4") (pintype "passive+no_connect"))
    )
    (net (code "55") (name "unconnected-(J801-Pad5)") (class "Default")
      (node (ref "J801") (pin "5") (pintype "passive+no_connect"))
    )
    (net (code "56") (name "unconnected-(U800-IN2L-Pad26)") (class "Default")
      (node (ref "U800") (pin "26") (pinfunction "IN2L_26") (pintype "input+no_connect"))
    )
    (net (code "57") (name "unconnected-(U800-IN2R-Pad24)") (class "Default")
      (node (ref "U800") (pin "24") (pinfunction "IN2R_24") (pintype "input+no_connect"))
    )
    (net (code "58") (name "unconnected-(U801-AUX_OUT-Pad4)") (class "Default")
      (node (ref "U801") (pin "4") (pinfunction "AUX_OUT_4") (pintype "output"))
    )
  )
)
